# Pi_Cap.net
KiCad netlist of a schematic drawn in EAGLE
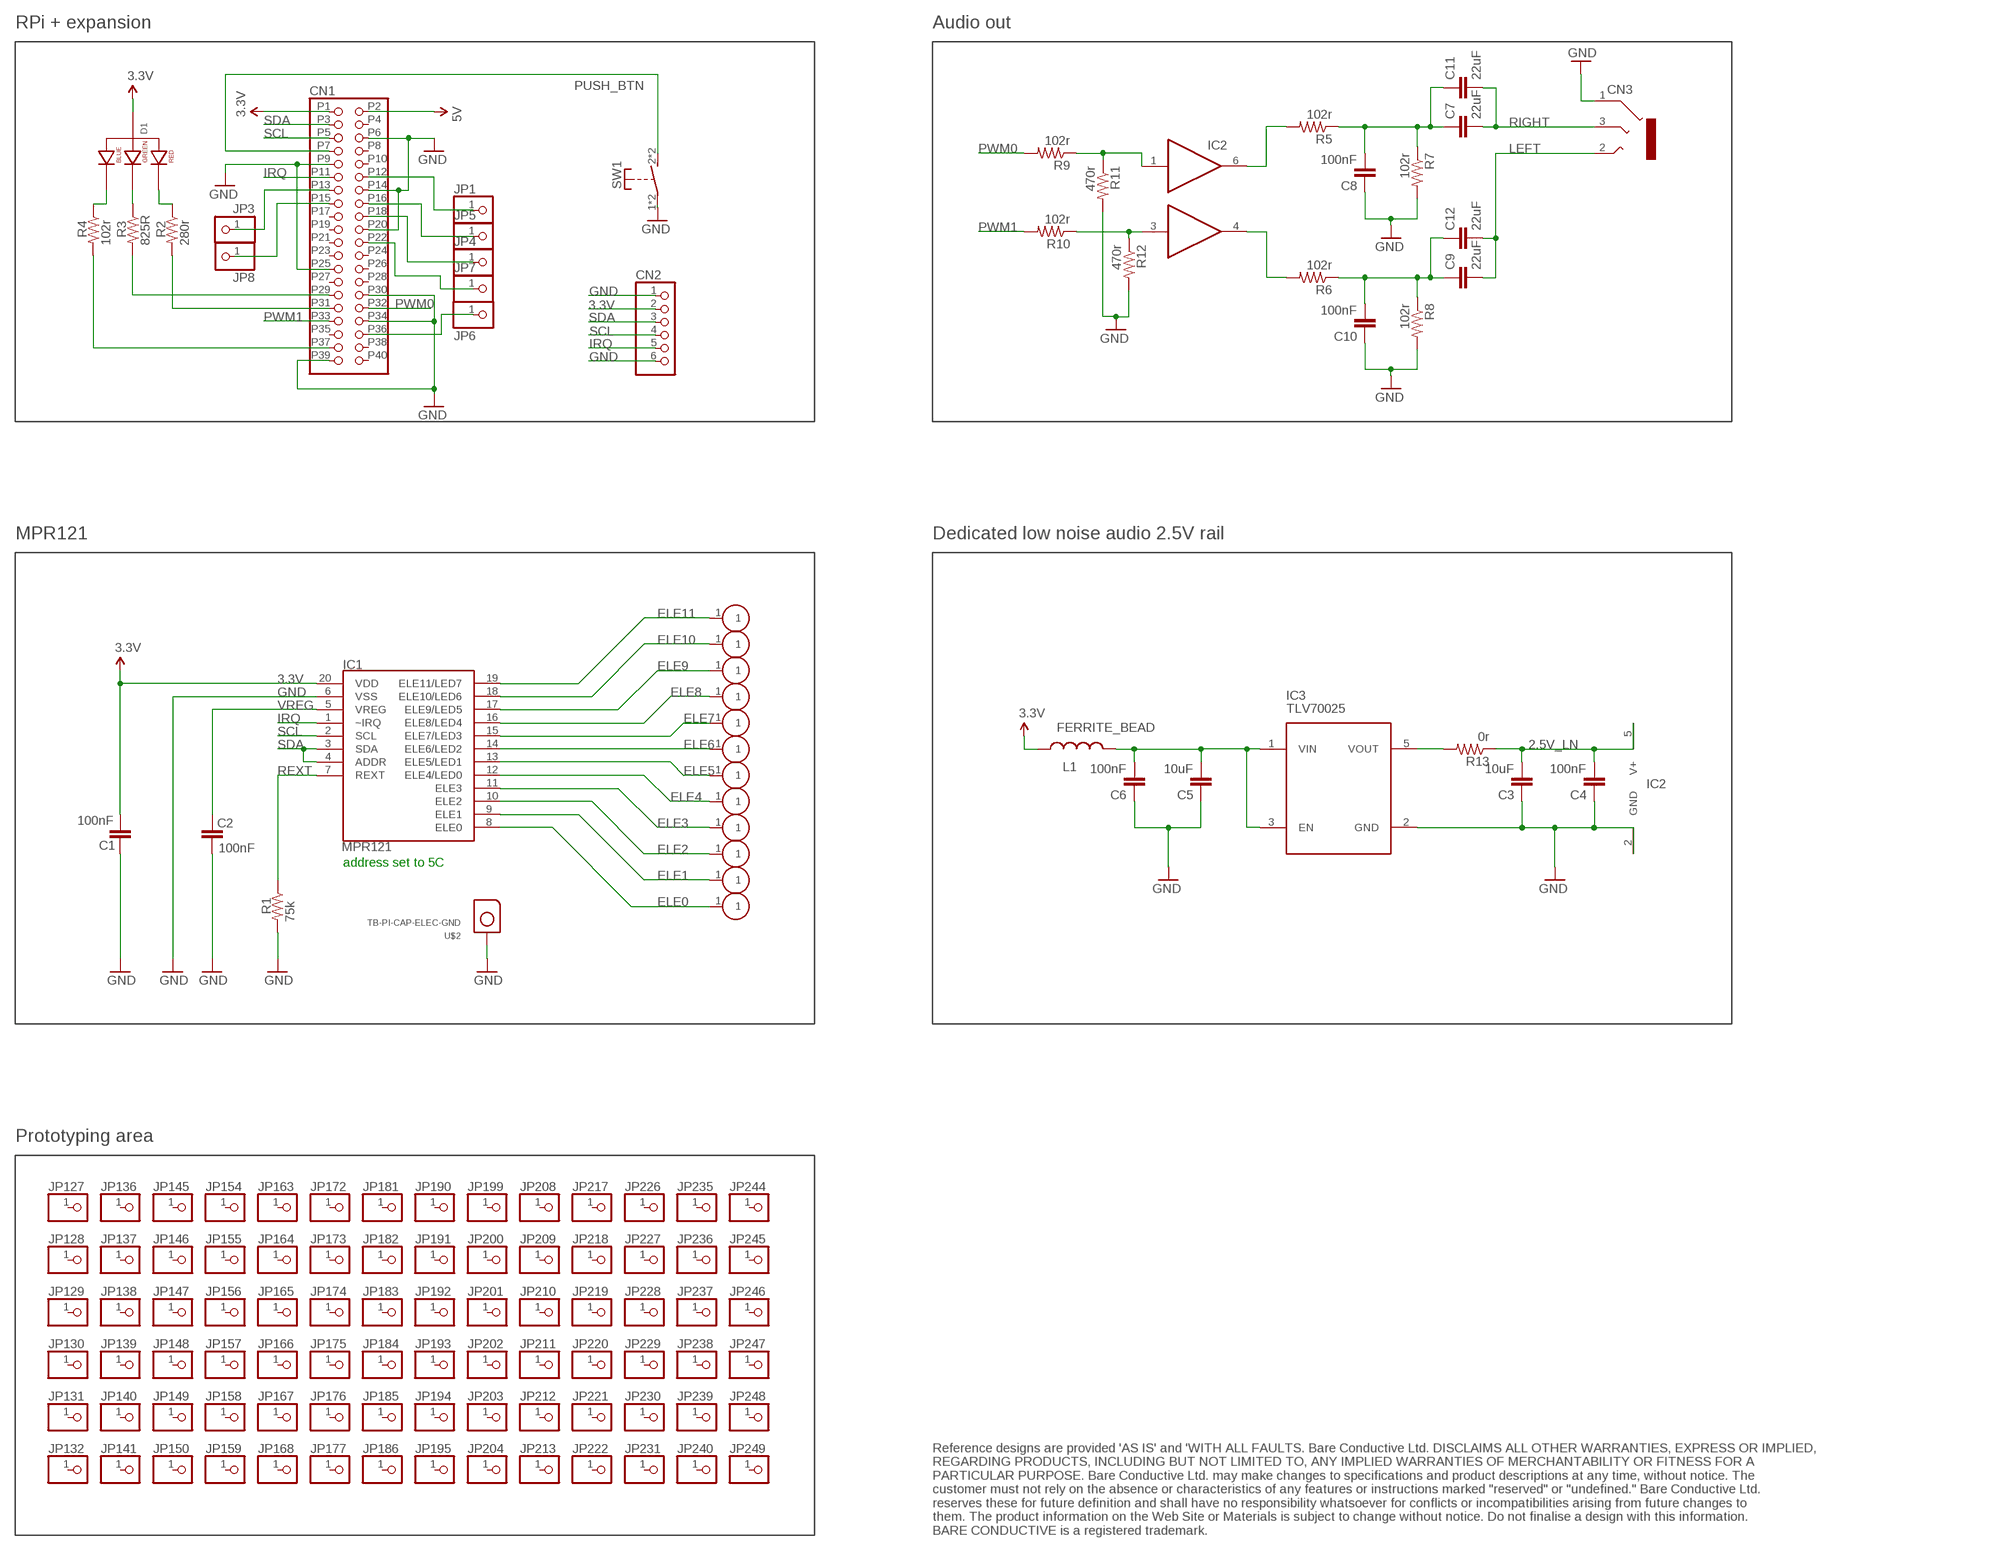
[diagram p0: schematic, sheet 1]

(export (version "E")
  (design (tool "Eeschema 10.0.6"))
  (components
    (comp (ref "C1")
      (value "100nF")
      (footprint "eagle-import:0402-CAP")
      (libsource (lib "eagle-import") (part "CAP0402-CAP"))
    )
    (comp (ref "C2")
      (value "100nF")
      (footprint "eagle-import:0402-CAP")
      (libsource (lib "eagle-import") (part "CAP0402-CAP"))
    )
    (comp (ref "C3")
      (value "10uF")
      (footprint "eagle-import:1206")
      (libsource (lib "eagle-import") (part "SparkFun-Passives_CAP1206"))
    )
    (comp (ref "C4")
      (value "100nF")
      (footprint "eagle-import:0402-CAP")
      (libsource (lib "eagle-import") (part "CAP0402-CAP"))
    )
    (comp (ref "C5")
      (value "10uF")
      (footprint "eagle-import:1206")
      (libsource (lib "eagle-import") (part "SparkFun-Passives_CAP1206"))
    )
    (comp (ref "C6")
      (value "100nF")
      (footprint "eagle-import:0402-CAP")
      (libsource (lib "eagle-import") (part "CAP0402-CAP"))
    )
    (comp (ref "C7")
      (value "22uF")
      (footprint "eagle-import:1206")
      (libsource (lib "eagle-import") (part "SparkFun-Passives_CAP1206"))
    )
    (comp (ref "C8")
      (value "100nF")
      (footprint "eagle-import:0402-CAP")
      (libsource (lib "eagle-import") (part "SparkFun-Passives_CAP0402-CAP"))
    )
    (comp (ref "C9")
      (value "22uF")
      (footprint "eagle-import:1206")
      (libsource (lib "eagle-import") (part "SparkFun-Passives_CAP1206"))
    )
    (comp (ref "C10")
      (value "100nF")
      (footprint "eagle-import:0402-CAP")
      (libsource (lib "eagle-import") (part "SparkFun-Passives_CAP0402-CAP"))
    )
    (comp (ref "C11")
      (value "22uF")
      (footprint "eagle-import:1206")
      (libsource (lib "eagle-import") (part "SparkFun-Passives_CAP1206"))
    )
    (comp (ref "C12")
      (value "22uF")
      (footprint "eagle-import:1206")
      (libsource (lib "eagle-import") (part "SparkFun-Passives_CAP1206"))
    )
    (comp (ref "CN1")
      (value "PINHD-2X20/2X20_SMD")
      (footprint "eagle-import:2X20_SMD")
      (libsource (lib "eagle-import") (part "PINHD-2X20/2X20_SMD"))
    )
    (comp (ref "CN2")
      (value "6W_0.5MM_FFC_RA_SMD")
      (footprint "eagle-import:6W_0.5MM_FFC_RA_SMD")
      (libsource (lib "eagle-import") (part "6W_0.5MM_FFC_RA"))
    )
    (comp (ref "CN3")
      (value "STEREO_SOCKET")
      (footprint "eagle-import:SMD_STEREO_SOCKET")
      (libsource (lib "eagle-import") (part "SMD_STEREO_SOCKET"))
    )
    (comp (ref "D1")
      (value "PLCC4_RGB_LED")
      (footprint "eagle-import:LED-3528")
      (libsource (lib "eagle-import") (part "LED_RGB_CA"))
    )
    (comp (ref "IC1")
      (value "MPR121")
      (footprint "eagle-import:QFN-20-0.4MM")
      (libsource (lib "eagle-import") (part "MPR121QFN20"))
    )
    (comp (ref "IC2")
      (value "DUAL_BUFFER")
      (footprint "eagle-import:SOT-363")
      (libsource (lib "eagle-import") (part "74LVC2G34GW"))
    )
    (comp (ref "IC3")
      (value "TLV70025")
      (footprint "eagle-import:SC70")
      (libsource (lib "eagle-import") (part "TLV00XX"))
    )
    (comp (ref "JP1")
      (value "PINHD-1X1CB")
      (footprint "eagle-import:1X01-CLEANBIG")
      (libsource (lib "eagle-import") (part "PINHD-1X1CB"))
    )
    (comp (ref "JP3")
      (value "PINHD-1X1CB")
      (footprint "eagle-import:1X01-CLEANBIG")
      (libsource (lib "eagle-import") (part "PINHD-1X1CB"))
    )
    (comp (ref "JP4")
      (value "PINHD-1X1CB")
      (footprint "eagle-import:1X01-CLEANBIG")
      (libsource (lib "eagle-import") (part "PINHD-1X1CB"))
    )
    (comp (ref "JP5")
      (value "PINHD-1X1CB")
      (footprint "eagle-import:1X01-CLEANBIG")
      (libsource (lib "eagle-import") (part "PINHD-1X1CB"))
    )
    (comp (ref "JP6")
      (value "PINHD-1X1CB")
      (footprint "eagle-import:1X01-CLEANBIG")
      (libsource (lib "eagle-import") (part "PINHD-1X1CB"))
    )
    (comp (ref "JP7")
      (value "PINHD-1X1CB")
      (footprint "eagle-import:1X01-CLEANBIG")
      (libsource (lib "eagle-import") (part "PINHD-1X1CB"))
    )
    (comp (ref "JP8")
      (value "PINHD-1X1CB")
      (footprint "eagle-import:1X01-CLEANBIG")
      (libsource (lib "eagle-import") (part "PINHD-1X1CB"))
    )
    (comp (ref "JP127")
      (value "PINHD-1X1CB")
      (footprint "eagle-import:1X01-CLEANBIG")
      (libsource (lib "eagle-import") (part "PINHD-1X1CB"))
    )
    (comp (ref "JP128")
      (value "PINHD-1X1CB")
      (footprint "eagle-import:1X01-CLEANBIG")
      (libsource (lib "eagle-import") (part "PINHD-1X1CB"))
    )
    (comp (ref "JP129")
      (value "PINHD-1X1CB")
      (footprint "eagle-import:1X01-CLEANBIG")
      (libsource (lib "eagle-import") (part "PINHD-1X1CB"))
    )
    (comp (ref "JP130")
      (value "PINHD-1X1CB")
      (footprint "eagle-import:1X01-CLEANBIG")
      (libsource (lib "eagle-import") (part "PINHD-1X1CB"))
    )
    (comp (ref "JP131")
      (value "PINHD-1X1CB")
      (footprint "eagle-import:1X01-CLEANBIG")
      (libsource (lib "eagle-import") (part "PINHD-1X1CB"))
    )
    (comp (ref "JP132")
      (value "PINHD-1X1CB")
      (footprint "eagle-import:1X01-CLEANBIG")
      (libsource (lib "eagle-import") (part "PINHD-1X1CB"))
    )
    (comp (ref "JP136")
      (value "PINHD-1X1CB")
      (footprint "eagle-import:1X01-CLEANBIG")
      (libsource (lib "eagle-import") (part "PINHD-1X1CB"))
    )
    (comp (ref "JP137")
      (value "PINHD-1X1CB")
      (footprint "eagle-import:1X01-CLEANBIG")
      (libsource (lib "eagle-import") (part "PINHD-1X1CB"))
    )
    (comp (ref "JP138")
      (value "PINHD-1X1CB")
      (footprint "eagle-import:1X01-CLEANBIG")
      (libsource (lib "eagle-import") (part "PINHD-1X1CB"))
    )
    (comp (ref "JP139")
      (value "PINHD-1X1CB")
      (footprint "eagle-import:1X01-CLEANBIG")
      (libsource (lib "eagle-import") (part "PINHD-1X1CB"))
    )
    (comp (ref "JP140")
      (value "PINHD-1X1CB")
      (footprint "eagle-import:1X01-CLEANBIG")
      (libsource (lib "eagle-import") (part "PINHD-1X1CB"))
    )
    (comp (ref "JP141")
      (value "PINHD-1X1CB")
      (footprint "eagle-import:1X01-CLEANBIG")
      (libsource (lib "eagle-import") (part "PINHD-1X1CB"))
    )
    (comp (ref "JP145")
      (value "PINHD-1X1CB")
      (footprint "eagle-import:1X01-CLEANBIG")
      (libsource (lib "eagle-import") (part "PINHD-1X1CB"))
    )
    (comp (ref "JP146")
      (value "PINHD-1X1CB")
      (footprint "eagle-import:1X01-CLEANBIG")
      (libsource (lib "eagle-import") (part "PINHD-1X1CB"))
    )
    (comp (ref "JP147")
      (value "PINHD-1X1CB")
      (footprint "eagle-import:1X01-CLEANBIG")
      (libsource (lib "eagle-import") (part "PINHD-1X1CB"))
    )
    (comp (ref "JP148")
      (value "PINHD-1X1CB")
      (footprint "eagle-import:1X01-CLEANBIG")
      (libsource (lib "eagle-import") (part "PINHD-1X1CB"))
    )
    (comp (ref "JP149")
      (value "PINHD-1X1CB")
      (footprint "eagle-import:1X01-CLEANBIG")
      (libsource (lib "eagle-import") (part "PINHD-1X1CB"))
    )
    (comp (ref "JP150")
      (value "PINHD-1X1CB")
      (footprint "eagle-import:1X01-CLEANBIG")
      (libsource (lib "eagle-import") (part "PINHD-1X1CB"))
    )
    (comp (ref "JP154")
      (value "PINHD-1X1CB")
      (footprint "eagle-import:1X01-CLEANBIG")
      (libsource (lib "eagle-import") (part "PINHD-1X1CB"))
    )
    (comp (ref "JP155")
      (value "PINHD-1X1CB")
      (footprint "eagle-import:1X01-CLEANBIG")
      (libsource (lib "eagle-import") (part "PINHD-1X1CB"))
    )
    (comp (ref "JP156")
      (value "PINHD-1X1CB")
      (footprint "eagle-import:1X01-CLEANBIG")
      (libsource (lib "eagle-import") (part "PINHD-1X1CB"))
    )
    (comp (ref "JP157")
      (value "PINHD-1X1CB")
      (footprint "eagle-import:1X01-CLEANBIG")
      (libsource (lib "eagle-import") (part "PINHD-1X1CB"))
    )
    (comp (ref "JP158")
      (value "PINHD-1X1CB")
      (footprint "eagle-import:1X01-CLEANBIG")
      (libsource (lib "eagle-import") (part "PINHD-1X1CB"))
    )
    (comp (ref "JP159")
      (value "PINHD-1X1CB")
      (footprint "eagle-import:1X01-CLEANBIG")
      (libsource (lib "eagle-import") (part "PINHD-1X1CB"))
    )
    (comp (ref "JP163")
      (value "PINHD-1X1CB")
      (footprint "eagle-import:1X01-CLEANBIG")
      (libsource (lib "eagle-import") (part "PINHD-1X1CB"))
    )
    (comp (ref "JP164")
      (value "PINHD-1X1CB")
      (footprint "eagle-import:1X01-CLEANBIG")
      (libsource (lib "eagle-import") (part "PINHD-1X1CB"))
    )
    (comp (ref "JP165")
      (value "PINHD-1X1CB")
      (footprint "eagle-import:1X01-CLEANBIG")
      (libsource (lib "eagle-import") (part "PINHD-1X1CB"))
    )
    (comp (ref "JP166")
      (value "PINHD-1X1CB")
      (footprint "eagle-import:1X01-CLEANBIG")
      (libsource (lib "eagle-import") (part "PINHD-1X1CB"))
    )
    (comp (ref "JP167")
      (value "PINHD-1X1CB")
      (footprint "eagle-import:1X01-CLEANBIG")
      (libsource (lib "eagle-import") (part "PINHD-1X1CB"))
    )
    (comp (ref "JP168")
      (value "PINHD-1X1CB")
      (footprint "eagle-import:1X01-CLEANBIG")
      (libsource (lib "eagle-import") (part "PINHD-1X1CB"))
    )
    (comp (ref "JP172")
      (value "PINHD-1X1CB")
      (footprint "eagle-import:1X01-CLEANBIG")
      (libsource (lib "eagle-import") (part "PINHD-1X1CB"))
    )
    (comp (ref "JP173")
      (value "PINHD-1X1CB")
      (footprint "eagle-import:1X01-CLEANBIG")
      (libsource (lib "eagle-import") (part "PINHD-1X1CB"))
    )
    (comp (ref "JP174")
      (value "PINHD-1X1CB")
      (footprint "eagle-import:1X01-CLEANBIG")
      (libsource (lib "eagle-import") (part "PINHD-1X1CB"))
    )
    (comp (ref "JP175")
      (value "PINHD-1X1CB")
      (footprint "eagle-import:1X01-CLEANBIG")
      (libsource (lib "eagle-import") (part "PINHD-1X1CB"))
    )
    (comp (ref "JP176")
      (value "PINHD-1X1CB")
      (footprint "eagle-import:1X01-CLEANBIG")
      (libsource (lib "eagle-import") (part "PINHD-1X1CB"))
    )
    (comp (ref "JP177")
      (value "PINHD-1X1CB")
      (footprint "eagle-import:1X01-CLEANBIG")
      (libsource (lib "eagle-import") (part "PINHD-1X1CB"))
    )
    (comp (ref "JP181")
      (value "PINHD-1X1CB")
      (footprint "eagle-import:1X01-CLEANBIG")
      (libsource (lib "eagle-import") (part "PINHD-1X1CB"))
    )
    (comp (ref "JP182")
      (value "PINHD-1X1CB")
      (footprint "eagle-import:1X01-CLEANBIG")
      (libsource (lib "eagle-import") (part "PINHD-1X1CB"))
    )
    (comp (ref "JP183")
      (value "PINHD-1X1CB")
      (footprint "eagle-import:1X01-CLEANBIG")
      (libsource (lib "eagle-import") (part "PINHD-1X1CB"))
    )
    (comp (ref "JP184")
      (value "PINHD-1X1CB")
      (footprint "eagle-import:1X01-CLEANBIG")
      (libsource (lib "eagle-import") (part "PINHD-1X1CB"))
    )
    (comp (ref "JP185")
      (value "PINHD-1X1CB")
      (footprint "eagle-import:1X01-CLEANBIG")
      (libsource (lib "eagle-import") (part "PINHD-1X1CB"))
    )
    (comp (ref "JP186")
      (value "PINHD-1X1CB")
      (footprint "eagle-import:1X01-CLEANBIG")
      (libsource (lib "eagle-import") (part "PINHD-1X1CB"))
    )
    (comp (ref "JP190")
      (value "PINHD-1X1CB")
      (footprint "eagle-import:1X01-CLEANBIG")
      (libsource (lib "eagle-import") (part "PINHD-1X1CB"))
    )
    (comp (ref "JP191")
      (value "PINHD-1X1CB")
      (footprint "eagle-import:1X01-CLEANBIG")
      (libsource (lib "eagle-import") (part "PINHD-1X1CB"))
    )
    (comp (ref "JP192")
      (value "PINHD-1X1CB")
      (footprint "eagle-import:1X01-CLEANBIG")
      (libsource (lib "eagle-import") (part "PINHD-1X1CB"))
    )
    (comp (ref "JP193")
      (value "PINHD-1X1CB")
      (footprint "eagle-import:1X01-CLEANBIG")
      (libsource (lib "eagle-import") (part "PINHD-1X1CB"))
    )
    (comp (ref "JP194")
      (value "PINHD-1X1CB")
      (footprint "eagle-import:1X01-CLEANBIG")
      (libsource (lib "eagle-import") (part "PINHD-1X1CB"))
    )
    (comp (ref "JP195")
      (value "PINHD-1X1CB")
      (footprint "eagle-import:1X01-CLEANBIG")
      (libsource (lib "eagle-import") (part "PINHD-1X1CB"))
    )
    (comp (ref "JP199")
      (value "PINHD-1X1CB")
      (footprint "eagle-import:1X01-CLEANBIG")
      (libsource (lib "eagle-import") (part "PINHD-1X1CB"))
    )
    (comp (ref "JP200")
      (value "PINHD-1X1CB")
      (footprint "eagle-import:1X01-CLEANBIG")
      (libsource (lib "eagle-import") (part "PINHD-1X1CB"))
    )
    (comp (ref "JP201")
      (value "PINHD-1X1CB")
      (footprint "eagle-import:1X01-CLEANBIG")
      (libsource (lib "eagle-import") (part "PINHD-1X1CB"))
    )
    (comp (ref "JP202")
      (value "PINHD-1X1CB")
      (footprint "eagle-import:1X01-CLEANBIG")
      (libsource (lib "eagle-import") (part "PINHD-1X1CB"))
    )
    (comp (ref "JP203")
      (value "PINHD-1X1CB")
      (footprint "eagle-import:1X01-CLEANBIG")
      (libsource (lib "eagle-import") (part "PINHD-1X1CB"))
    )
    (comp (ref "JP204")
      (value "PINHD-1X1CB")
      (footprint "eagle-import:1X01-CLEANBIG")
      (libsource (lib "eagle-import") (part "PINHD-1X1CB"))
    )
    (comp (ref "JP208")
      (value "PINHD-1X1CB")
      (footprint "eagle-import:1X01-CLEANBIG")
      (libsource (lib "eagle-import") (part "PINHD-1X1CB"))
    )
    (comp (ref "JP209")
      (value "PINHD-1X1CB")
      (footprint "eagle-import:1X01-CLEANBIG")
      (libsource (lib "eagle-import") (part "PINHD-1X1CB"))
    )
    (comp (ref "JP210")
      (value "PINHD-1X1CB")
      (footprint "eagle-import:1X01-CLEANBIG")
      (libsource (lib "eagle-import") (part "PINHD-1X1CB"))
    )
    (comp (ref "JP211")
      (value "PINHD-1X1CB")
      (footprint "eagle-import:1X01-CLEANBIG")
      (libsource (lib "eagle-import") (part "PINHD-1X1CB"))
    )
    (comp (ref "JP212")
      (value "PINHD-1X1CB")
      (footprint "eagle-import:1X01-CLEANBIG")
      (libsource (lib "eagle-import") (part "PINHD-1X1CB"))
    )
    (comp (ref "JP213")
      (value "PINHD-1X1CB")
      (footprint "eagle-import:1X01-CLEANBIG")
      (libsource (lib "eagle-import") (part "PINHD-1X1CB"))
    )
    (comp (ref "JP217")
      (value "PINHD-1X1CB")
      (footprint "eagle-import:1X01-CLEANBIG")
      (libsource (lib "eagle-import") (part "PINHD-1X1CB"))
    )
    (comp (ref "JP218")
      (value "PINHD-1X1CB")
      (footprint "eagle-import:1X01-CLEANBIG")
      (libsource (lib "eagle-import") (part "PINHD-1X1CB"))
    )
    (comp (ref "JP219")
      (value "PINHD-1X1CB")
      (footprint "eagle-import:1X01-CLEANBIG")
      (libsource (lib "eagle-import") (part "PINHD-1X1CB"))
    )
    (comp (ref "JP220")
      (value "PINHD-1X1CB")
      (footprint "eagle-import:1X01-CLEANBIG")
      (libsource (lib "eagle-import") (part "PINHD-1X1CB"))
    )
    (comp (ref "JP221")
      (value "PINHD-1X1CB")
      (footprint "eagle-import:1X01-CLEANBIG")
      (libsource (lib "eagle-import") (part "PINHD-1X1CB"))
    )
    (comp (ref "JP222")
      (value "PINHD-1X1CB")
      (footprint "eagle-import:1X01-CLEANBIG")
      (libsource (lib "eagle-import") (part "PINHD-1X1CB"))
    )
    (comp (ref "JP226")
      (value "PINHD-1X1CB")
      (footprint "eagle-import:1X01-CLEANBIG")
      (libsource (lib "eagle-import") (part "PINHD-1X1CB"))
    )
    (comp (ref "JP227")
      (value "PINHD-1X1CB")
      (footprint "eagle-import:1X01-CLEANBIG")
      (libsource (lib "eagle-import") (part "PINHD-1X1CB"))
    )
    (comp (ref "JP228")
      (value "PINHD-1X1CB")
      (footprint "eagle-import:1X01-CLEANBIG")
      (libsource (lib "eagle-import") (part "PINHD-1X1CB"))
    )
    (comp (ref "JP229")
      (value "PINHD-1X1CB")
      (footprint "eagle-import:1X01-CLEANBIG")
      (libsource (lib "eagle-import") (part "PINHD-1X1CB"))
    )
    (comp (ref "JP230")
      (value "PINHD-1X1CB")
      (footprint "eagle-import:1X01-CLEANBIG")
      (libsource (lib "eagle-import") (part "PINHD-1X1CB"))
    )
    (comp (ref "JP231")
      (value "PINHD-1X1CB")
      (footprint "eagle-import:1X01-CLEANBIG")
      (libsource (lib "eagle-import") (part "PINHD-1X1CB"))
    )
    (comp (ref "JP235")
      (value "PINHD-1X1CB")
      (footprint "eagle-import:1X01-CLEANBIG")
      (libsource (lib "eagle-import") (part "PINHD-1X1CB"))
    )
    (comp (ref "JP236")
      (value "PINHD-1X1CB")
      (footprint "eagle-import:1X01-CLEANBIG")
      (libsource (lib "eagle-import") (part "PINHD-1X1CB"))
    )
    (comp (ref "JP237")
      (value "PINHD-1X1CB")
      (footprint "eagle-import:1X01-CLEANBIG")
      (libsource (lib "eagle-import") (part "PINHD-1X1CB"))
    )
    (comp (ref "JP238")
      (value "PINHD-1X1CB")
      (footprint "eagle-import:1X01-CLEANBIG")
      (libsource (lib "eagle-import") (part "PINHD-1X1CB"))
    )
    (comp (ref "JP239")
      (value "PINHD-1X1CB")
      (footprint "eagle-import:1X01-CLEANBIG")
      (libsource (lib "eagle-import") (part "PINHD-1X1CB"))
    )
    (comp (ref "JP240")
      (value "PINHD-1X1CB")
      (footprint "eagle-import:1X01-CLEANBIG")
      (libsource (lib "eagle-import") (part "PINHD-1X1CB"))
    )
    (comp (ref "JP244")
      (value "PINHD-1X1CB")
      (footprint "eagle-import:1X01-CLEANBIG")
      (libsource (lib "eagle-import") (part "PINHD-1X1CB"))
    )
    (comp (ref "JP245")
      (value "PINHD-1X1CB")
      (footprint "eagle-import:1X01-CLEANBIG")
      (libsource (lib "eagle-import") (part "PINHD-1X1CB"))
    )
    (comp (ref "JP246")
      (value "PINHD-1X1CB")
      (footprint "eagle-import:1X01-CLEANBIG")
      (libsource (lib "eagle-import") (part "PINHD-1X1CB"))
    )
    (comp (ref "JP247")
      (value "PINHD-1X1CB")
      (footprint "eagle-import:1X01-CLEANBIG")
      (libsource (lib "eagle-import") (part "PINHD-1X1CB"))
    )
    (comp (ref "JP248")
      (value "PINHD-1X1CB")
      (footprint "eagle-import:1X01-CLEANBIG")
      (libsource (lib "eagle-import") (part "PINHD-1X1CB"))
    )
    (comp (ref "JP249")
      (value "PINHD-1X1CB")
      (footprint "eagle-import:1X01-CLEANBIG")
      (libsource (lib "eagle-import") (part "PINHD-1X1CB"))
    )
    (comp (ref "L1")
      (value "FERRITE_BEAD")
      (footprint "eagle-import:C0402")
      (libsource (lib "eagle-import") (part "INDUCTOR0402"))
    )
    (comp (ref "R1")
      (value "75k")
      (footprint "eagle-import:0402-RES")
      (libsource (lib "eagle-import") (part "RESISTOR0402-RES"))
    )
    (comp (ref "R2")
      (value "280r")
      (footprint "eagle-import:0402-RES")
      (libsource (lib "eagle-import") (part "RESISTOR0402-RES"))
    )
    (comp (ref "R3")
      (value "825R")
      (footprint "eagle-import:0402-RES")
      (libsource (lib "eagle-import") (part "RESISTOR0402-RES"))
    )
    (comp (ref "R4")
      (value "102r")
      (footprint "eagle-import:0402-RES")
      (libsource (lib "eagle-import") (part "RESISTOR0402-RES"))
    )
    (comp (ref "R5")
      (value "102r")
      (footprint "eagle-import:0402-RES")
      (libsource (lib "eagle-import") (part "SparkFun-Passives_RESISTOR0402-RES"))
    )
    (comp (ref "R6")
      (value "102r")
      (footprint "eagle-import:0402-RES")
      (libsource (lib "eagle-import") (part "SparkFun-Passives_RESISTOR0402-RES"))
    )
    (comp (ref "R7")
      (value "102r")
      (footprint "eagle-import:0402-RES")
      (libsource (lib "eagle-import") (part "SparkFun-Passives_RESISTOR0402-RES"))
    )
    (comp (ref "R8")
      (value "102r")
      (footprint "eagle-import:0402-RES")
      (libsource (lib "eagle-import") (part "SparkFun-Passives_RESISTOR0402-RES"))
    )
    (comp (ref "R9")
      (value "102r")
      (footprint "eagle-import:0402-RES")
      (libsource (lib "eagle-import") (part "SparkFun-Passives_RESISTOR0402-RES"))
    )
    (comp (ref "R10")
      (value "102r")
      (footprint "eagle-import:0402-RES")
      (libsource (lib "eagle-import") (part "SparkFun-Passives_RESISTOR0402-RES"))
    )
    (comp (ref "R11")
      (value "470r")
      (footprint "eagle-import:0402-RES")
      (libsource (lib "eagle-import") (part "SparkFun-Passives_RESISTOR0402-RES"))
    )
    (comp (ref "R12")
      (value "470r")
      (footprint "eagle-import:0402-RES")
      (libsource (lib "eagle-import") (part "SparkFun-Passives_RESISTOR0402-RES"))
    )
    (comp (ref "R13")
      (value "0r")
      (footprint "eagle-import:0402-RES")
      (libsource (lib "eagle-import") (part "SparkFun-Passives_RESISTOR0402-RES"))
    )
    (comp (ref "SW1")
      (value "SMD_RA_PUSH_SW")
      (footprint "eagle-import:SMD_RA_PUSH_SW")
      (libsource (lib "eagle-import") (part "SMD_RA_PUSH_SW"))
    )
    (comp (ref "U$1")
      (value "EDGE-ELEC-LEFT")
      (footprint "eagle-import:EDGE-ELEC-LEFT")
      (libsource (lib "eagle-import") (part "EDGE-ELEC-LEFT"))
    )
    (comp (ref "U$2")
      (value "TB-PI-CAP-ELEC-GND")
      (footprint "eagle-import:TB-PI-CAP-ELEC-GND")
      (libsource (lib "eagle-import") (part "TB-PI-CAP-ELEC-GND"))
    )
    (comp (ref "U$3")
      (value "EDGE-ELEC-RIGHT")
      (footprint "eagle-import:EDGE-ELEC-RIGHT")
      (libsource (lib "eagle-import") (part "EDGE-ELEC-RIGHT"))
    )
    (comp (ref "U$17")
      (value "EDGE-ELEC")
      (footprint "eagle-import:EDGE-ELEC")
      (libsource (lib "eagle-import") (part "EDGE-ELEC"))
    )
    (comp (ref "U$18")
      (value "EDGE-ELEC")
      (footprint "eagle-import:EDGE-ELEC")
      (libsource (lib "eagle-import") (part "EDGE-ELEC"))
    )
    (comp (ref "U$22")
      (value "EDGE-ELEC")
      (footprint "eagle-import:EDGE-ELEC")
      (libsource (lib "eagle-import") (part "EDGE-ELEC"))
    )
    (comp (ref "U$24")
      (value "EDGE-ELEC")
      (footprint "eagle-import:EDGE-ELEC")
      (libsource (lib "eagle-import") (part "EDGE-ELEC"))
    )
    (comp (ref "U$26")
      (value "EDGE-ELEC")
      (footprint "eagle-import:EDGE-ELEC")
      (libsource (lib "eagle-import") (part "EDGE-ELEC"))
    )
    (comp (ref "U$27")
      (value "EDGE-ELEC")
      (footprint "eagle-import:EDGE-ELEC")
      (libsource (lib "eagle-import") (part "EDGE-ELEC"))
    )
    (comp (ref "U$28")
      (value "EDGE-ELEC")
      (footprint "eagle-import:EDGE-ELEC")
      (libsource (lib "eagle-import") (part "EDGE-ELEC"))
    )
    (comp (ref "U$29")
      (value "EDGE-ELEC")
      (footprint "eagle-import:EDGE-ELEC")
      (libsource (lib "eagle-import") (part "EDGE-ELEC"))
    )
    (comp (ref "U$30")
      (value "EDGE-ELEC")
      (footprint "eagle-import:EDGE-ELEC")
      (libsource (lib "eagle-import") (part "EDGE-ELEC"))
    )
    (comp (ref "U$31")
      (value "EDGE-ELEC")
      (footprint "eagle-import:EDGE-ELEC")
      (libsource (lib "eagle-import") (part "EDGE-ELEC"))
    )
  )
  (nets
    (net (code "1") (name "/2.5V_LN") (class "Default")
      (node (ref "C3") (pin "2") (pinfunction "2_2") (pintype "passive"))
      (node (ref "C4") (pin "2") (pinfunction "2_2") (pintype "passive"))
      (node (ref "IC2") (pin "5") (pinfunction "V+_5") (pintype "bidirectional"))
      (node (ref "R13") (pin "1") (pinfunction "1_1") (pintype "passive"))
    )
    (net (code "2") (name "/ELE0") (class "Default")
      (node (ref "IC1") (pin "8") (pinfunction "ELE0_8") (pintype "bidirectional"))
      (node (ref "U$1") (pin "1") (pinfunction "1_1") (pintype "bidirectional"))
    )
    (net (code "3") (name "/ELE1") (class "Default")
      (node (ref "IC1") (pin "9") (pinfunction "ELE1_9") (pintype "bidirectional"))
      (node (ref "U$31") (pin "1") (pinfunction "1_1") (pintype "bidirectional"))
    )
    (net (code "4") (name "/ELE2") (class "Default")
      (node (ref "IC1") (pin "10") (pinfunction "ELE2_10") (pintype "bidirectional"))
      (node (ref "U$30") (pin "1") (pinfunction "1_1") (pintype "bidirectional"))
    )
    (net (code "5") (name "/ELE3") (class "Default")
      (node (ref "IC1") (pin "11") (pinfunction "ELE3_11") (pintype "bidirectional"))
      (node (ref "U$29") (pin "1") (pinfunction "1_1") (pintype "bidirectional"))
    )
    (net (code "6") (name "/ELE4") (class "Default")
      (node (ref "IC1") (pin "12") (pinfunction "ELE4/LED0_12") (pintype "bidirectional"))
      (node (ref "U$28") (pin "1") (pinfunction "1_1") (pintype "bidirectional"))
    )
    (net (code "7") (name "/ELE5") (class "Default")
      (node (ref "IC1") (pin "13") (pinfunction "ELE5/LED1_13") (pintype "bidirectional"))
      (node (ref "U$27") (pin "1") (pinfunction "1_1") (pintype "bidirectional"))
    )
    (net (code "8") (name "/ELE6") (class "Default")
      (node (ref "IC1") (pin "14") (pinfunction "ELE6/LED2_14") (pintype "bidirectional"))
      (node (ref "U$26") (pin "1") (pinfunction "1_1") (pintype "bidirectional"))
    )
    (net (code "9") (name "/ELE7") (class "Default")
      (node (ref "IC1") (pin "15") (pinfunction "ELE7/LED3_15") (pintype "bidirectional"))
      (node (ref "U$24") (pin "1") (pinfunction "1_1") (pintype "bidirectional"))
    )
    (net (code "10") (name "/ELE8") (class "Default")
      (node (ref "IC1") (pin "16") (pinfunction "ELE8/LED4_16") (pintype "bidirectional"))
      (node (ref "U$22") (pin "1") (pinfunction "1_1") (pintype "bidirectional"))
    )
    (net (code "11") (name "/ELE9") (class "Default")
      (node (ref "IC1") (pin "17") (pinfunction "ELE9/LED5_17") (pintype "bidirectional"))
      (node (ref "U$18") (pin "1") (pinfunction "1_1") (pintype "bidirectional"))
    )
    (net (code "12") (name "/ELE10") (class "Default")
      (node (ref "IC1") (pin "18") (pinfunction "ELE10/LED6_18") (pintype "bidirectional"))
      (node (ref "U$17") (pin "1") (pinfunction "1_1") (pintype "bidirectional"))
    )
    (net (code "13") (name "/ELE11") (class "Default")
      (node (ref "IC1") (pin "19") (pinfunction "ELE11/LED7_19") (pintype "bidirectional"))
      (node (ref "U$3") (pin "1") (pinfunction "1_1") (pintype "bidirectional"))
    )
    (net (code "14") (name "/IRQ") (class "Default")
      (node (ref "CN1") (pin "P11") (pinfunction "11_P11") (pintype "passive"))
      (node (ref "CN2") (pin "5") (pinfunction "5_5") (pintype "passive"))
      (node (ref "IC1") (pin "1") (pinfunction "~{IRQ}_1") (pintype "bidirectional"))
    )
    (net (code "15") (name "/LEFT") (class "Default")
      (node (ref "C12") (pin "2") (pinfunction "2_2") (pintype "passive"))
      (node (ref "C9") (pin "2") (pinfunction "2_2") (pintype "passive"))
      (node (ref "CN3") (pin "2") (pinfunction "2_2") (pintype "passive"))
    )
    (net (code "16") (name "/PUSH_BTN") (class "Default")
      (node (ref "CN1") (pin "P7") (pinfunction "7_P7") (pintype "passive"))
      (node (ref "SW1") (pin "2") (pinfunction "S_2") (pintype "passive"))
      (node (ref "SW1") (pin "4") (pinfunction "S_4") (pintype "passive"))
    )
    (net (code "17") (name "/PWM0") (class "Default")
      (node (ref "CN1") (pin "P32") (pinfunction "32_P32") (pintype "passive"))
      (node (ref "R9") (pin "2") (pinfunction "2_2") (pintype "passive"))
    )
    (net (code "18") (name "/PWM1") (class "Default")
      (node (ref "CN1") (pin "P33") (pinfunction "33_P33") (pintype "passive"))
      (node (ref "R10") (pin "2") (pinfunction "2_2") (pintype "passive"))
    )
    (net (code "19") (name "/REXT") (class "Default")
      (node (ref "IC1") (pin "7") (pinfunction "REXT_7") (pintype "bidirectional"))
      (node (ref "R1") (pin "1") (pinfunction "1_1") (pintype "passive"))
    )
    (net (code "20") (name "/RIGHT") (class "Default")
      (node (ref "C11") (pin "2") (pinfunction "2_2") (pintype "passive"))
      (node (ref "C7") (pin "2") (pinfunction "2_2") (pintype "passive"))
      (node (ref "CN3") (pin "3") (pinfunction "3_3") (pintype "passive"))
    )
    (net (code "21") (name "/SCL") (class "Default")
      (node (ref "CN1") (pin "P5") (pinfunction "5_P5") (pintype "passive"))
      (node (ref "CN2") (pin "4") (pinfunction "4_4") (pintype "passive"))
      (node (ref "IC1") (pin "2") (pinfunction "SCL_2") (pintype "bidirectional"))
    )
    (net (code "22") (name "/SDA") (class "Default")
      (node (ref "CN1") (pin "P3") (pinfunction "3_P3") (pintype "passive"))
      (node (ref "CN2") (pin "3") (pinfunction "3_3") (pintype "passive"))
      (node (ref "IC1") (pin "3") (pinfunction "SDA_3") (pintype "bidirectional"))
      (node (ref "IC1") (pin "4") (pinfunction "ADDR_4") (pintype "bidirectional"))
    )
    (net (code "23") (name "/VREG") (class "Default")
      (node (ref "C2") (pin "2") (pinfunction "2_2") (pintype "passive"))
      (node (ref "IC1") (pin "5") (pinfunction "VREG_5") (pintype "bidirectional"))
    )
    (net (code "24") (name "3.3V") (class "Default")
      (node (ref "C1") (pin "1") (pinfunction "1_1") (pintype "passive"))
      (node (ref "CN1") (pin "P1") (pinfunction "1_P1") (pintype "passive"))
      (node (ref "CN2") (pin "2") (pinfunction "2_2") (pintype "passive"))
      (node (ref "D1") (pin "1") (pinfunction "ANODE_1") (pintype "bidirectional"))
      (node (ref "IC1") (pin "20") (pinfunction "VDD_20") (pintype "bidirectional"))
      (node (ref "L1") (pin "1") (pinfunction "1_1") (pintype "passive"))
    )
    (net (code "25") (name "5V") (class "Default")
      (node (ref "CN1") (pin "P2") (pinfunction "2_P2") (pintype "passive"))
    )
    (net (code "26") (name "GND") (class "Default")
      (node (ref "C1") (pin "2") (pinfunction "2_2") (pintype "passive"))
      (node (ref "C10") (pin "1") (pinfunction "1_1") (pintype "passive"))
      (node (ref "C2") (pin "1") (pinfunction "1_1") (pintype "passive"))
      (node (ref "C3") (pin "1") (pinfunction "1_1") (pintype "passive"))
      (node (ref "C4") (pin "1") (pinfunction "1_1") (pintype "passive"))
      (node (ref "C5") (pin "1") (pinfunction "1_1") (pintype "passive"))
      (node (ref "C6") (pin "1") (pinfunction "1_1") (pintype "passive"))
      (node (ref "C8") (pin "1") (pinfunction "1_1") (pintype "passive"))
      (node (ref "CN1") (pin "P14") (pinfunction "14_P14") (pintype "passive"))
      (node (ref "CN1") (pin "P20") (pinfunction "20_P20") (pintype "passive"))
      (node (ref "CN1") (pin "P25") (pinfunction "25_P25") (pintype "passive"))
      (node (ref "CN1") (pin "P30") (pinfunction "30_P30") (pintype "passive"))
      (node (ref "CN1") (pin "P34") (pinfunction "34_P34") (pintype "passive"))
      (node (ref "CN1") (pin "P39") (pinfunction "39_P39") (pintype "passive"))
      (node (ref "CN1") (pin "P6") (pinfunction "6_P6") (pintype "passive"))
      (node (ref "CN1") (pin "P9") (pinfunction "9_P9") (pintype "passive"))
      (node (ref "CN2") (pin "1") (pinfunction "1_1") (pintype "passive"))
      (node (ref "CN2") (pin "6") (pinfunction "6_6") (pintype "passive"))
      (node (ref "CN3") (pin "1") (pinfunction "1_1") (pintype "passive"))
      (node (ref "IC1") (pin "6") (pinfunction "VSS_6") (pintype "bidirectional"))
      (node (ref "IC2") (pin "2") (pinfunction "GND_2") (pintype "bidirectional"))
      (node (ref "IC3") (pin "2") (pinfunction "GND_2") (pintype "bidirectional"))
      (node (ref "R1") (pin "2") (pinfunction "2_2") (pintype "passive"))
      (node (ref "R11") (pin "2") (pinfunction "2_2") (pintype "passive"))
      (node (ref "R12") (pin "2") (pinfunction "2_2") (pintype "passive"))
      (node (ref "R7") (pin "2") (pinfunction "2_2") (pintype "passive"))
      (node (ref "R8") (pin "2") (pinfunction "2_2") (pintype "passive"))
      (node (ref "SW1") (pin "1") (pinfunction "P_1") (pintype "passive"))
      (node (ref "SW1") (pin "3") (pinfunction "P_3") (pintype "passive"))
      (node (ref "U$2") (pin "1") (pinfunction "P$1_1") (pintype "bidirectional"))
    )
    (net (code "27") (name "Net-(C10-Pad2)") (class "Default")
      (node (ref "C10") (pin "2") (pinfunction "2_2") (pintype "passive"))
      (node (ref "C12") (pin "1") (pinfunction "1_1") (pintype "passive"))
      (node (ref "C9") (pin "1") (pinfunction "1_1") (pintype "passive"))
      (node (ref "R6") (pin "1") (pinfunction "1_1") (pintype "passive"))
      (node (ref "R8") (pin "1") (pinfunction "1_1") (pintype "passive"))
    )
    (net (code "28") (name "Net-(C11-Pad1)") (class "Default")
      (node (ref "C11") (pin "1") (pinfunction "1_1") (pintype "passive"))
      (node (ref "C7") (pin "1") (pinfunction "1_1") (pintype "passive"))
      (node (ref "C8") (pin "2") (pinfunction "2_2") (pintype "passive"))
      (node (ref "R5") (pin "1") (pinfunction "1_1") (pintype "passive"))
      (node (ref "R7") (pin "1") (pinfunction "1_1") (pintype "passive"))
    )
    (net (code "29") (name "Net-(CN1-12)") (class "Default")
      (node (ref "CN1") (pin "P12") (pinfunction "12_P12") (pintype "passive"))
      (node (ref "JP1") (pin "1") (pinfunction "1_1") (pintype "passive"))
    )
    (net (code "30") (name "Net-(CN1-13)") (class "Default")
      (node (ref "CN1") (pin "P13") (pinfunction "13_P13") (pintype "passive"))
      (node (ref "JP3") (pin "1") (pinfunction "1_1") (pintype "passive"))
    )
    (net (code "31") (name "Net-(CN1-15)") (class "Default")
      (node (ref "CN1") (pin "P15") (pinfunction "15_P15") (pintype "passive"))
      (node (ref "JP8") (pin "1") (pinfunction "1_1") (pintype "passive"))
    )
    (net (code "32") (name "Net-(CN1-16)") (class "Default")
      (node (ref "CN1") (pin "P16") (pinfunction "16_P16") (pintype "passive"))
      (node (ref "JP5") (pin "1") (pinfunction "1_1") (pintype "passive"))
    )
    (net (code "33") (name "Net-(CN1-18)") (class "Default")
      (node (ref "CN1") (pin "P18") (pinfunction "18_P18") (pintype "passive"))
      (node (ref "JP4") (pin "1") (pinfunction "1_1") (pintype "passive"))
    )
    (net (code "34") (name "Net-(CN1-22)") (class "Default")
      (node (ref "CN1") (pin "P22") (pinfunction "22_P22") (pintype "passive"))
      (node (ref "JP7") (pin "1") (pinfunction "1_1") (pintype "passive"))
    )
    (net (code "35") (name "Net-(CN1-29)") (class "Default")
      (node (ref "CN1") (pin "P29") (pinfunction "29_P29") (pintype "passive"))
      (node (ref "R3") (pin "2") (pinfunction "2_2") (pintype "passive"))
    )
    (net (code "36") (name "Net-(CN1-31)") (class "Default")
      (node (ref "CN1") (pin "P31") (pinfunction "31_P31") (pintype "passive"))
      (node (ref "R2") (pin "2") (pinfunction "2_2") (pintype "passive"))
    )
    (net (code "37") (name "Net-(CN1-36)") (class "Default")
      (node (ref "CN1") (pin "P36") (pinfunction "36_P36") (pintype "passive"))
      (node (ref "JP6") (pin "1") (pinfunction "1_1") (pintype "passive"))
    )
    (net (code "38") (name "Net-(CN1-37)") (class "Default")
      (node (ref "CN1") (pin "P37") (pinfunction "37_P37") (pintype "passive"))
      (node (ref "R4") (pin "2") (pinfunction "2_2") (pintype "passive"))
    )
    (net (code "39") (name "Net-(D1-BLUE_CATHODE)") (class "Default")
      (node (ref "D1") (pin "2") (pinfunction "BLUE_CATHODE_2") (pintype "bidirectional"))
      (node (ref "R4") (pin "1") (pinfunction "1_1") (pintype "passive"))
    )
    (net (code "40") (name "Net-(D1-GREEN_CATHODE)") (class "Default")
      (node (ref "D1") (pin "4") (pinfunction "GREEN_CATHODE_4") (pintype "bidirectional"))
      (node (ref "R3") (pin "1") (pinfunction "1_1") (pintype "passive"))
    )
    (net (code "41") (name "Net-(D1-RED_CATHODE)") (class "Default")
      (node (ref "D1") (pin "3") (pinfunction "RED_CATHODE_3") (pintype "bidirectional"))
      (node (ref "R2") (pin "1") (pinfunction "1_1") (pintype "passive"))
    )
    (net (code "42") (name "Net-(IC2A-IN_1)") (class "Default")
      (node (ref "IC2") (pin "1") (pinfunction "IN_1_1") (pintype "input"))
      (node (ref "R11") (pin "1") (pinfunction "1_1") (pintype "passive"))
      (node (ref "R9") (pin "1") (pinfunction "1_1") (pintype "passive"))
    )
    (net (code "43") (name "Net-(IC2A-IN_2)") (class "Default")
      (node (ref "IC2") (pin "3") (pinfunction "IN_2_3") (pintype "input"))
      (node (ref "R10") (pin "1") (pinfunction "1_1") (pintype "passive"))
      (node (ref "R12") (pin "1") (pinfunction "1_1") (pintype "passive"))
    )
    (net (code "44") (name "Net-(IC2A-OUT_1)") (class "Default")
      (node (ref "IC2") (pin "6") (pinfunction "OUT_1_6") (pintype "bidirectional"))
      (node (ref "R5") (pin "2") (pinfunction "2_2") (pintype "passive"))
    )
    (net (code "45") (name "Net-(IC2A-OUT_2)") (class "Default")
      (node (ref "IC2") (pin "4") (pinfunction "OUT_2_4") (pintype "output"))
      (node (ref "R6") (pin "2") (pinfunction "2_2") (pintype "passive"))
    )
    (net (code "46") (name "Net-(IC3-EN)") (class "Default")
      (node (ref "C5") (pin "2") (pinfunction "2_2") (pintype "passive"))
      (node (ref "C6") (pin "2") (pinfunction "2_2") (pintype "passive"))
      (node (ref "IC3") (pin "1") (pinfunction "VIN_1") (pintype "bidirectional"))
      (node (ref "IC3") (pin "3") (pinfunction "EN_3") (pintype "bidirectional"))
      (node (ref "L1") (pin "2") (pinfunction "2_2") (pintype "passive"))
    )
    (net (code "47") (name "Net-(IC3-VOUT)") (class "Default")
      (node (ref "IC3") (pin "5") (pinfunction "VOUT_5") (pintype "bidirectional"))
      (node (ref "R13") (pin "2") (pinfunction "2_2") (pintype "passive"))
    )
    (net (code "48") (name "unconnected-(CN1-4-PadP4)") (class "Default")
      (node (ref "CN1") (pin "P4") (pinfunction "4_P4") (pintype "passive"))
    )
    (net (code "49") (name "unconnected-(CN1-8-PadP8)") (class "Default")
      (node (ref "CN1") (pin "P8") (pinfunction "8_P8") (pintype "passive"))
    )
    (net (code "50") (name "unconnected-(CN1-10-PadP10)") (class "Default")
      (node (ref "CN1") (pin "P10") (pinfunction "10_P10") (pintype "passive"))
    )
    (net (code "51") (name "unconnected-(CN1-17-PadP17)") (class "Default")
      (node (ref "CN1") (pin "P17") (pinfunction "17_P17") (pintype "passive"))
    )
    (net (code "52") (name "unconnected-(CN1-19-PadP19)") (class "Default")
      (node (ref "CN1") (pin "P19") (pinfunction "19_P19") (pintype "passive"))
    )
    (net (code "53") (name "unconnected-(CN1-21-PadP21)") (class "Default")
      (node (ref "CN1") (pin "P21") (pinfunction "21_P21") (pintype "passive"))
    )
    (net (code "54") (name "unconnected-(CN1-23-PadP23)") (class "Default")
      (node (ref "CN1") (pin "P23") (pinfunction "23_P23") (pintype "passive"))
    )
    (net (code "55") (name "unconnected-(CN1-24-PadP24)") (class "Default")
      (node (ref "CN1") (pin "P24") (pinfunction "24_P24") (pintype "passive"))
    )
    (net (code "56") (name "unconnected-(CN1-26-PadP26)") (class "Default")
      (node (ref "CN1") (pin "P26") (pinfunction "26_P26") (pintype "passive"))
    )
    (net (code "57") (name "unconnected-(CN1-27-PadP27)") (class "Default")
      (node (ref "CN1") (pin "P27") (pinfunction "27_P27") (pintype "passive"))
    )
    (net (code "58") (name "unconnected-(CN1-28-PadP28)") (class "Default")
      (node (ref "CN1") (pin "P28") (pinfunction "28_P28") (pintype "passive"))
    )
    (net (code "59") (name "unconnected-(CN1-35-PadP35)") (class "Default")
      (node (ref "CN1") (pin "P35") (pinfunction "35_P35") (pintype "passive"))
    )
    (net (code "60") (name "unconnected-(CN1-38-PadP38)") (class "Default")
      (node (ref "CN1") (pin "P38") (pinfunction "38_P38") (pintype "passive"))
    )
    (net (code "61") (name "unconnected-(CN1-40-PadP40)") (class "Default")
      (node (ref "CN1") (pin "P40") (pinfunction "40_P40") (pintype "passive"))
    )
    (net (code "62") (name "unconnected-(JP127-Pad1)") (class "Default")
      (node (ref "JP127") (pin "1") (pinfunction "1_1") (pintype "passive"))
    )
    (net (code "63") (name "unconnected-(JP128-Pad1)") (class "Default")
      (node (ref "JP128") (pin "1") (pinfunction "1_1") (pintype "passive"))
    )
    (net (code "64") (name "unconnected-(JP129-Pad1)") (class "Default")
      (node (ref "JP129") (pin "1") (pinfunction "1_1") (pintype "passive"))
    )
    (net (code "65") (name "unconnected-(JP130-Pad1)") (class "Default")
      (node (ref "JP130") (pin "1") (pinfunction "1_1") (pintype "passive"))
    )
    (net (code "66") (name "unconnected-(JP131-Pad1)") (class "Default")
      (node (ref "JP131") (pin "1") (pinfunction "1_1") (pintype "passive"))
    )
    (net (code "67") (name "unconnected-(JP132-Pad1)") (class "Default")
      (node (ref "JP132") (pin "1") (pinfunction "1_1") (pintype "passive"))
    )
    (net (code "68") (name "unconnected-(JP136-Pad1)") (class "Default")
      (node (ref "JP136") (pin "1") (pinfunction "1_1") (pintype "passive"))
    )
    (net (code "69") (name "unconnected-(JP137-Pad1)") (class "Default")
      (node (ref "JP137") (pin "1") (pinfunction "1_1") (pintype "passive"))
    )
    (net (code "70") (name "unconnected-(JP138-Pad1)") (class "Default")
      (node (ref "JP138") (pin "1") (pinfunction "1_1") (pintype "passive"))
    )
    (net (code "71") (name "unconnected-(JP139-Pad1)") (class "Default")
      (node (ref "JP139") (pin "1") (pinfunction "1_1") (pintype "passive"))
    )
    (net (code "72") (name "unconnected-(JP140-Pad1)") (class "Default")
      (node (ref "JP140") (pin "1") (pinfunction "1_1") (pintype "passive"))
    )
    (net (code "73") (name "unconnected-(JP141-Pad1)") (class "Default")
      (node (ref "JP141") (pin "1") (pinfunction "1_1") (pintype "passive"))
    )
    (net (code "74") (name "unconnected-(JP145-Pad1)") (class "Default")
      (node (ref "JP145") (pin "1") (pinfunction "1_1") (pintype "passive"))
    )
    (net (code "75") (name "unconnected-(JP146-Pad1)") (class "Default")
      (node (ref "JP146") (pin "1") (pinfunction "1_1") (pintype "passive"))
    )
    (net (code "76") (name "unconnected-(JP147-Pad1)") (class "Default")
      (node (ref "JP147") (pin "1") (pinfunction "1_1") (pintype "passive"))
    )
    (net (code "77") (name "unconnected-(JP148-Pad1)") (class "Default")
      (node (ref "JP148") (pin "1") (pinfunction "1_1") (pintype "passive"))
    )
    (net (code "78") (name "unconnected-(JP149-Pad1)") (class "Default")
      (node (ref "JP149") (pin "1") (pinfunction "1_1") (pintype "passive"))
    )
    (net (code "79") (name "unconnected-(JP150-Pad1)") (class "Default")
      (node (ref "JP150") (pin "1") (pinfunction "1_1") (pintype "passive"))
    )
    (net (code "80") (name "unconnected-(JP154-Pad1)") (class "Default")
      (node (ref "JP154") (pin "1") (pinfunction "1_1") (pintype "passive"))
    )
    (net (code "81") (name "unconnected-(JP155-Pad1)") (class "Default")
      (node (ref "JP155") (pin "1") (pinfunction "1_1") (pintype "passive"))
    )
    (net (code "82") (name "unconnected-(JP156-Pad1)") (class "Default")
      (node (ref "JP156") (pin "1") (pinfunction "1_1") (pintype "passive"))
    )
    (net (code "83") (name "unconnected-(JP157-Pad1)") (class "Default")
      (node (ref "JP157") (pin "1") (pinfunction "1_1") (pintype "passive"))
    )
    (net (code "84") (name "unconnected-(JP158-Pad1)") (class "Default")
      (node (ref "JP158") (pin "1") (pinfunction "1_1") (pintype "passive"))
    )
    (net (code "85") (name "unconnected-(JP159-Pad1)") (class "Default")
      (node (ref "JP159") (pin "1") (pinfunction "1_1") (pintype "passive"))
    )
    (net (code "86") (name "unconnected-(JP163-Pad1)") (class "Default")
      (node (ref "JP163") (pin "1") (pinfunction "1_1") (pintype "passive"))
    )
    (net (code "87") (name "unconnected-(JP164-Pad1)") (class "Default")
      (node (ref "JP164") (pin "1") (pinfunction "1_1") (pintype "passive"))
    )
    (net (code "88") (name "unconnected-(JP165-Pad1)") (class "Default")
      (node (ref "JP165") (pin "1") (pinfunction "1_1") (pintype "passive"))
    )
    (net (code "89") (name "unconnected-(JP166-Pad1)") (class "Default")
      (node (ref "JP166") (pin "1") (pinfunction "1_1") (pintype "passive"))
    )
    (net (code "90") (name "unconnected-(JP167-Pad1)") (class "Default")
      (node (ref "JP167") (pin "1") (pinfunction "1_1") (pintype "passive"))
    )
    (net (code "91") (name "unconnected-(JP168-Pad1)") (class "Default")
      (node (ref "JP168") (pin "1") (pinfunction "1_1") (pintype "passive"))
    )
    (net (code "92") (name "unconnected-(JP172-Pad1)") (class "Default")
      (node (ref "JP172") (pin "1") (pinfunction "1_1") (pintype "passive"))
    )
    (net (code "93") (name "unconnected-(JP173-Pad1)") (class "Default")
      (node (ref "JP173") (pin "1") (pinfunction "1_1") (pintype "passive"))
    )
    (net (code "94") (name "unconnected-(JP174-Pad1)") (class "Default")
      (node (ref "JP174") (pin "1") (pinfunction "1_1") (pintype "passive"))
    )
    (net (code "95") (name "unconnected-(JP175-Pad1)") (class "Default")
      (node (ref "JP175") (pin "1") (pinfunction "1_1") (pintype "passive"))
    )
    (net (code "96") (name "unconnected-(JP176-Pad1)") (class "Default")
      (node (ref "JP176") (pin "1") (pinfunction "1_1") (pintype "passive"))
    )
    (net (code "97") (name "unconnected-(JP177-Pad1)") (class "Default")
      (node (ref "JP177") (pin "1") (pinfunction "1_1") (pintype "passive"))
    )
    (net (code "98") (name "unconnected-(JP181-Pad1)") (class "Default")
      (node (ref "JP181") (pin "1") (pinfunction "1_1") (pintype "passive"))
    )
    (net (code "99") (name "unconnected-(JP182-Pad1)") (class "Default")
      (node (ref "JP182") (pin "1") (pinfunction "1_1") (pintype "passive"))
    )
    (net (code "100") (name "unconnected-(JP183-Pad1)") (class "Default")
      (node (ref "JP183") (pin "1") (pinfunction "1_1") (pintype "passive"))
    )
    (net (code "101") (name "unconnected-(JP184-Pad1)") (class "Default")
      (node (ref "JP184") (pin "1") (pinfunction "1_1") (pintype "passive"))
    )
    (net (code "102") (name "unconnected-(JP185-Pad1)") (class "Default")
      (node (ref "JP185") (pin "1") (pinfunction "1_1") (pintype "passive"))
    )
    (net (code "103") (name "unconnected-(JP186-Pad1)") (class "Default")
      (node (ref "JP186") (pin "1") (pinfunction "1_1") (pintype "passive"))
    )
    (net (code "104") (name "unconnected-(JP190-Pad1)") (class "Default")
      (node (ref "JP190") (pin "1") (pinfunction "1_1") (pintype "passive"))
    )
    (net (code "105") (name "unconnected-(JP191-Pad1)") (class "Default")
      (node (ref "JP191") (pin "1") (pinfunction "1_1") (pintype "passive"))
    )
    (net (code "106") (name "unconnected-(JP192-Pad1)") (class "Default")
      (node (ref "JP192") (pin "1") (pinfunction "1_1") (pintype "passive"))
    )
    (net (code "107") (name "unconnected-(JP193-Pad1)") (class "Default")
      (node (ref "JP193") (pin "1") (pinfunction "1_1") (pintype "passive"))
    )
    (net (code "108") (name "unconnected-(JP194-Pad1)") (class "Default")
      (node (ref "JP194") (pin "1") (pinfunction "1_1") (pintype "passive"))
    )
    (net (code "109") (name "unconnected-(JP195-Pad1)") (class "Default")
      (node (ref "JP195") (pin "1") (pinfunction "1_1") (pintype "passive"))
    )
    (net (code "110") (name "unconnected-(JP199-Pad1)") (class "Default")
      (node (ref "JP199") (pin "1") (pinfunction "1_1") (pintype "passive"))
    )
    (net (code "111") (name "unconnected-(JP200-Pad1)") (class "Default")
      (node (ref "JP200") (pin "1") (pinfunction "1_1") (pintype "passive"))
    )
    (net (code "112") (name "unconnected-(JP201-Pad1)") (class "Default")
      (node (ref "JP201") (pin "1") (pinfunction "1_1") (pintype "passive"))
    )
    (net (code "113") (name "unconnected-(JP202-Pad1)") (class "Default")
      (node (ref "JP202") (pin "1") (pinfunction "1_1") (pintype "passive"))
    )
    (net (code "114") (name "unconnected-(JP203-Pad1)") (class "Default")
      (node (ref "JP203") (pin "1") (pinfunction "1_1") (pintype "passive"))
    )
    (net (code "115") (name "unconnected-(JP204-Pad1)") (class "Default")
      (node (ref "JP204") (pin "1") (pinfunction "1_1") (pintype "passive"))
    )
    (net (code "116") (name "unconnected-(JP208-Pad1)") (class "Default")
      (node (ref "JP208") (pin "1") (pinfunction "1_1") (pintype "passive"))
    )
    (net (code "117") (name "unconnected-(JP209-Pad1)") (class "Default")
      (node (ref "JP209") (pin "1") (pinfunction "1_1") (pintype "passive"))
    )
    (net (code "118") (name "unconnected-(JP210-Pad1)") (class "Default")
      (node (ref "JP210") (pin "1") (pinfunction "1_1") (pintype "passive"))
    )
    (net (code "119") (name "unconnected-(JP211-Pad1)") (class "Default")
      (node (ref "JP211") (pin "1") (pinfunction "1_1") (pintype "passive"))
    )
    (net (code "120") (name "unconnected-(JP212-Pad1)") (class "Default")
      (node (ref "JP212") (pin "1") (pinfunction "1_1") (pintype "passive"))
    )
    (net (code "121") (name "unconnected-(JP213-Pad1)") (class "Default")
      (node (ref "JP213") (pin "1") (pinfunction "1_1") (pintype "passive"))
    )
    (net (code "122") (name "unconnected-(JP217-Pad1)") (class "Default")
      (node (ref "JP217") (pin "1") (pinfunction "1_1") (pintype "passive"))
    )
    (net (code "123") (name "unconnected-(JP218-Pad1)") (class "Default")
      (node (ref "JP218") (pin "1") (pinfunction "1_1") (pintype "passive"))
    )
    (net (code "124") (name "unconnected-(JP219-Pad1)") (class "Default")
      (node (ref "JP219") (pin "1") (pinfunction "1_1") (pintype "passive"))
    )
    (net (code "125") (name "unconnected-(JP220-Pad1)") (class "Default")
      (node (ref "JP220") (pin "1") (pinfunction "1_1") (pintype "passive"))
    )
    (net (code "126") (name "unconnected-(JP221-Pad1)") (class "Default")
      (node (ref "JP221") (pin "1") (pinfunction "1_1") (pintype "passive"))
    )
    (net (code "127") (name "unconnected-(JP222-Pad1)") (class "Default")
      (node (ref "JP222") (pin "1") (pinfunction "1_1") (pintype "passive"))
    )
    (net (code "128") (name "unconnected-(JP226-Pad1)") (class "Default")
      (node (ref "JP226") (pin "1") (pinfunction "1_1") (pintype "passive"))
    )
    (net (code "129") (name "unconnected-(JP227-Pad1)") (class "Default")
      (node (ref "JP227") (pin "1") (pinfunction "1_1") (pintype "passive"))
    )
    (net (code "130") (name "unconnected-(JP228-Pad1)") (class "Default")
      (node (ref "JP228") (pin "1") (pinfunction "1_1") (pintype "passive"))
    )
    (net (code "131") (name "unconnected-(JP229-Pad1)") (class "Default")
      (node (ref "JP229") (pin "1") (pinfunction "1_1") (pintype "passive"))
    )
    (net (code "132") (name "unconnected-(JP230-Pad1)") (class "Default")
      (node (ref "JP230") (pin "1") (pinfunction "1_1") (pintype "passive"))
    )
    (net (code "133") (name "unconnected-(JP231-Pad1)") (class "Default")
      (node (ref "JP231") (pin "1") (pinfunction "1_1") (pintype "passive"))
    )
    (net (code "134") (name "unconnected-(JP235-Pad1)") (class "Default")
      (node (ref "JP235") (pin "1") (pinfunction "1_1") (pintype "passive"))
    )
    (net (code "135") (name "unconnected-(JP236-Pad1)") (class "Default")
      (node (ref "JP236") (pin "1") (pinfunction "1_1") (pintype "passive"))
    )
    (net (code "136") (name "unconnected-(JP237-Pad1)") (class "Default")
      (node (ref "JP237") (pin "1") (pinfunction "1_1") (pintype "passive"))
    )
    (net (code "137") (name "unconnected-(JP238-Pad1)") (class "Default")
      (node (ref "JP238") (pin "1") (pinfunction "1_1") (pintype "passive"))
    )
    (net (code "138") (name "unconnected-(JP239-Pad1)") (class "Default")
      (node (ref "JP239") (pin "1") (pinfunction "1_1") (pintype "passive"))
    )
    (net (code "139") (name "unconnected-(JP240-Pad1)") (class "Default")
      (node (ref "JP240") (pin "1") (pinfunction "1_1") (pintype "passive"))
    )
    (net (code "140") (name "unconnected-(JP244-Pad1)") (class "Default")
      (node (ref "JP244") (pin "1") (pinfunction "1_1") (pintype "passive"))
    )
    (net (code "141") (name "unconnected-(JP245-Pad1)") (class "Default")
      (node (ref "JP245") (pin "1") (pinfunction "1_1") (pintype "passive"))
    )
    (net (code "142") (name "unconnected-(JP246-Pad1)") (class "Default")
      (node (ref "JP246") (pin "1") (pinfunction "1_1") (pintype "passive"))
    )
    (net (code "143") (name "unconnected-(JP247-Pad1)") (class "Default")
      (node (ref "JP247") (pin "1") (pinfunction "1_1") (pintype "passive"))
    )
    (net (code "144") (name "unconnected-(JP248-Pad1)") (class "Default")
      (node (ref "JP248") (pin "1") (pinfunction "1_1") (pintype "passive"))
    )
    (net (code "145") (name "unconnected-(JP249-Pad1)") (class "Default")
      (node (ref "JP249") (pin "1") (pinfunction "1_1") (pintype "passive"))
    )
  )
)
